# power_board2_v2_0.net
KiCad netlist of a schematic drawn in EAGLE
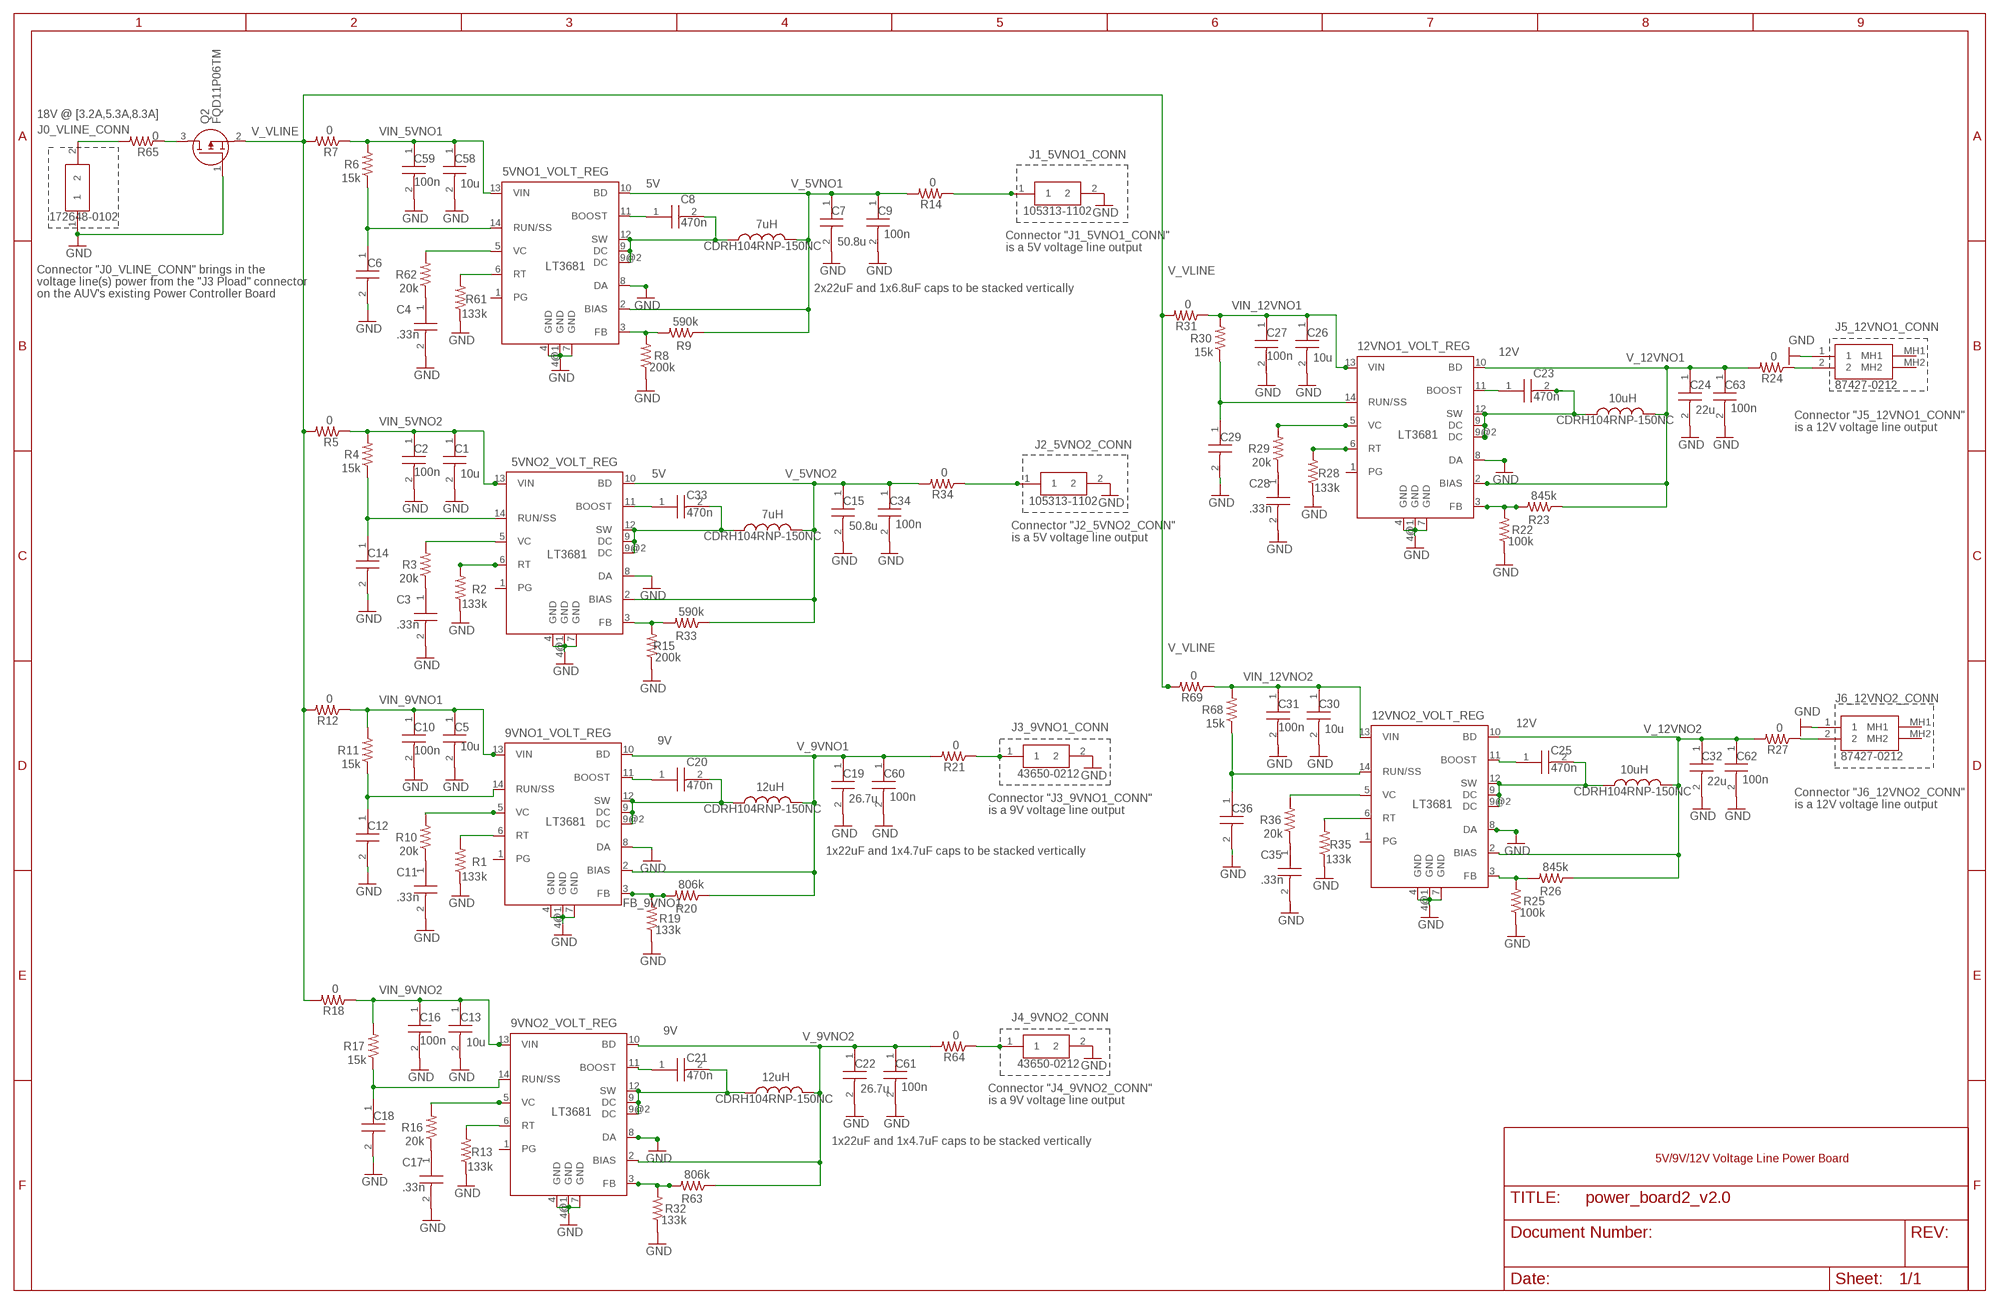
[diagram p0: schematic, sheet 1]

(export (version "E")
  (design (tool "Eeschema 10.0.6"))
  (components
    (comp (ref "5VNO1_VOLT_REG")
      (value "LT3681")
      (footprint "eagle-import:DFN14-4X3DE")
      (fields (field (name "MPN") "LT3681EDE#PBF"))
      (libsource (lib "eagle-import") (part "LT3681"))
    )
    (comp (ref "5VNO2_VOLT_REG")
      (value "LT3681")
      (footprint "eagle-import:DFN14-4X3DE")
      (fields (field (name "MPN") "LT3681EDE#PBF"))
      (libsource (lib "eagle-import") (part "LT3681"))
    )
    (comp (ref "9VNO1_VOLT_REG")
      (value "LT3681")
      (footprint "eagle-import:DFN14-4X3DE")
      (fields (field (name "MPN") "LT3681EDE#PBF"))
      (libsource (lib "eagle-import") (part "LT3681"))
    )
    (comp (ref "9VNO2_VOLT_REG")
      (value "LT3681")
      (footprint "eagle-import:DFN14-4X3DE")
      (fields (field (name "MPN") "LT3681EDE#PBF"))
      (libsource (lib "eagle-import") (part "LT3681"))
    )
    (comp (ref "12VNO1_VOLT_REG")
      (value "LT3681")
      (footprint "eagle-import:DFN14-4X3DE")
      (fields (field (name "MPN") "LT3681EDE#PBF"))
      (libsource (lib "eagle-import") (part "LT3681"))
    )
    (comp (ref "12VNO2_VOLT_REG")
      (value "LT3681")
      (footprint "eagle-import:DFN14-4X3DE")
      (fields (field (name "MPN") "LT3681EDE#PBF"))
      (libsource (lib "eagle-import") (part "LT3681"))
    )
    (comp (ref "C1")
      (value "10u")
      (footprint "eagle-import:CAPC5750X279N")
      (fields
        (field (name "MANUFACTURER_PART_NUMBER") "22201C106KAT2A")
        (field (name "MOUSER_PART_NUMBER") "581-22201C106KAT2A")
      )
      (libsource (lib "eagle-import") (part "22201C106KAT2A"))
    )
    (comp (ref "C2")
      (value "100n")
      (footprint "eagle-import:CAPC1608X90N")
      (fields
        (field (name "MANUFACTURER_PART_NUMBER") "06031C104KAT2A")
        (field (name "MOUSER_PART_NUMBER") "581-06031C104KAT2A")
      )
      (libsource (lib "eagle-import") (part "06031C104KAT2A"))
    )
    (comp (ref "C3")
      (value ".33n")
      (footprint "eagle-import:CAPC2012X140N")
      (fields
        (field (name "MANUFACTURER_PART_NUMBER") "08053C334KAT2A")
        (field (name "MOUSER_PART_NUMBER") "581-08053C334KAT2A")
        (field (name "RS_PART_NUMBER") "1747387")
      )
      (libsource (lib "eagle-import") (part "08053C334KAT2A"))
    )
    (comp (ref "C4")
      (value ".33n")
      (footprint "eagle-import:CAPC2012X140N")
      (fields
        (field (name "MANUFACTURER_PART_NUMBER") "08053C334KAT2A")
        (field (name "MOUSER_PART_NUMBER") "581-08053C334KAT2A")
        (field (name "RS_PART_NUMBER") "1747387")
      )
      (libsource (lib "eagle-import") (part "08053C334KAT2A"))
    )
    (comp (ref "C5")
      (value "10u")
      (footprint "eagle-import:CAPC5750X279N")
      (fields
        (field (name "MANUFACTURER_PART_NUMBER") "22201C106KAT2A")
        (field (name "MOUSER_PART_NUMBER") "581-22201C106KAT2A")
      )
      (libsource (lib "eagle-import") (part "22201C106KAT2A"))
    )
    (comp (ref "C6")
      (value "220n")
      (footprint "eagle-import:CAPC2012X140N")
      (fields
        (field (name "MANUFACTURER_PART_NUMBER") "08051C224KAT2A")
        (field (name "MOUSER_PART_NUMBER") "581-08051C224KAT2A")
      )
      (libsource (lib "eagle-import") (part "08051C224KAT2A"))
    )
    (comp (ref "C7")
      (value "50.8u")
      (footprint "eagle-import:CAPC3225X279N")
      (fields
        (field (name "MANUFACTURER_PART_NUMBER") "12103C226KAT2A")
        (field (name "MOUSER_PART_NUMBER") "581-12103C226KAT2A")
      )
      (libsource (lib "eagle-import") (part "12103C226KAT2A"))
    )
    (comp (ref "C8")
      (value "470n")
      (footprint "eagle-import:CAPC1608X90N")
      (fields
        (field (name "MANUFACTURER_PART_NUMBER") "06033C474JAT2A")
        (field (name "MOUSER_PART_NUMBER") "581-06033C474JAT2A")
      )
      (libsource (lib "eagle-import") (part "06033C474JAT2A"))
    )
    (comp (ref "C9")
      (value "100n")
      (footprint "eagle-import:CAPC1608X90N")
      (fields
        (field (name "MANUFACTURER_PART_NUMBER") "06033C104KAT4A")
        (field (name "MOUSER_PART_NUMBER") "581-06033C104KAT4A")
      )
      (libsource (lib "eagle-import") (part "06033C104KAT4A"))
    )
    (comp (ref "C10")
      (value "100n")
      (footprint "eagle-import:CAPC1608X90N")
      (fields
        (field (name "MANUFACTURER_PART_NUMBER") "06031C104KAT2A")
        (field (name "MOUSER_PART_NUMBER") "581-06031C104KAT2A")
      )
      (libsource (lib "eagle-import") (part "06031C104KAT2A"))
    )
    (comp (ref "C11")
      (value ".33n")
      (footprint "eagle-import:CAPC2012X140N")
      (fields
        (field (name "MANUFACTURER_PART_NUMBER") "08053C334KAT2A")
        (field (name "MOUSER_PART_NUMBER") "581-08053C334KAT2A")
        (field (name "RS_PART_NUMBER") "1747387")
      )
      (libsource (lib "eagle-import") (part "08053C334KAT2A"))
    )
    (comp (ref "C12")
      (value "220n")
      (footprint "eagle-import:CAPC2012X140N")
      (fields
        (field (name "MANUFACTURER_PART_NUMBER") "08051C224KAT2A")
        (field (name "MOUSER_PART_NUMBER") "581-08051C224KAT2A")
      )
      (libsource (lib "eagle-import") (part "08051C224KAT2A"))
    )
    (comp (ref "C13")
      (value "10u")
      (footprint "eagle-import:CAPC5750X279N")
      (fields
        (field (name "MANUFACTURER_PART_NUMBER") "22201C106KAT2A")
        (field (name "MOUSER_PART_NUMBER") "581-22201C106KAT2A")
      )
      (libsource (lib "eagle-import") (part "22201C106KAT2A"))
    )
    (comp (ref "C14")
      (value "220n")
      (footprint "eagle-import:CAPC2012X140N")
      (fields
        (field (name "MANUFACTURER_PART_NUMBER") "08051C224KAT2A")
        (field (name "MOUSER_PART_NUMBER") "581-08051C224KAT2A")
      )
      (libsource (lib "eagle-import") (part "08051C224KAT2A"))
    )
    (comp (ref "C15")
      (value "50.8u")
      (footprint "eagle-import:CAPC3225X279N")
      (fields
        (field (name "MANUFACTURER_PART_NUMBER") "12103C226KAT2A")
        (field (name "MOUSER_PART_NUMBER") "581-12103C226KAT2A")
      )
      (libsource (lib "eagle-import") (part "12103C226KAT2A"))
    )
    (comp (ref "C16")
      (value "100n")
      (footprint "eagle-import:CAPC1608X90N")
      (fields
        (field (name "MANUFACTURER_PART_NUMBER") "06031C104KAT2A")
        (field (name "MOUSER_PART_NUMBER") "581-06031C104KAT2A")
      )
      (libsource (lib "eagle-import") (part "06031C104KAT2A"))
    )
    (comp (ref "C17")
      (value ".33n")
      (footprint "eagle-import:CAPC2012X140N")
      (fields
        (field (name "MANUFACTURER_PART_NUMBER") "08053C334KAT2A")
        (field (name "MOUSER_PART_NUMBER") "581-08053C334KAT2A")
        (field (name "RS_PART_NUMBER") "1747387")
      )
      (libsource (lib "eagle-import") (part "08053C334KAT2A"))
    )
    (comp (ref "C18")
      (value "220n")
      (footprint "eagle-import:CAPC2012X140N")
      (fields
        (field (name "MANUFACTURER_PART_NUMBER") "08051C224KAT2A")
        (field (name "MOUSER_PART_NUMBER") "581-08051C224KAT2A")
      )
      (libsource (lib "eagle-import") (part "08051C224KAT2A"))
    )
    (comp (ref "C19")
      (value "26.7u")
      (footprint "eagle-import:CAPC3225X279N")
      (fields
        (field (name "MANUFACTURER_PART_NUMBER") "12103C226KAT2A")
        (field (name "MOUSER_PART_NUMBER") "581-12103C226KAT2A")
      )
      (libsource (lib "eagle-import") (part "12103C226KAT2A"))
    )
    (comp (ref "C20")
      (value "470n")
      (footprint "eagle-import:CAPC1608X90N")
      (fields
        (field (name "MANUFACTURER_PART_NUMBER") "06033C474JAT2A")
        (field (name "MOUSER_PART_NUMBER") "581-06033C474JAT2A")
      )
      (libsource (lib "eagle-import") (part "06033C474JAT2A"))
    )
    (comp (ref "C21")
      (value "470n")
      (footprint "eagle-import:CAPC1608X90N")
      (fields
        (field (name "MANUFACTURER_PART_NUMBER") "06033C474JAT2A")
        (field (name "MOUSER_PART_NUMBER") "581-06033C474JAT2A")
      )
      (libsource (lib "eagle-import") (part "06033C474JAT2A"))
    )
    (comp (ref "C22")
      (value "26.7u")
      (footprint "eagle-import:CAPC3225X279N")
      (fields
        (field (name "MANUFACTURER_PART_NUMBER") "12103C226KAT2A")
        (field (name "MOUSER_PART_NUMBER") "581-12103C226KAT2A")
      )
      (libsource (lib "eagle-import") (part "12103C226KAT2A"))
    )
    (comp (ref "C23")
      (value "470n")
      (footprint "eagle-import:CAPC1608X90N")
      (fields
        (field (name "MANUFACTURER_PART_NUMBER") "06033C474JAT2A")
        (field (name "MOUSER_PART_NUMBER") "581-06033C474JAT2A")
      )
      (libsource (lib "eagle-import") (part "06033C474JAT2A"))
    )
    (comp (ref "C24")
      (value "22u")
      (footprint "eagle-import:CAPC3225X279N")
      (fields
        (field (name "MANUFACTURER_PART_NUMBER") "12103C226KAT2A")
        (field (name "MOUSER_PART_NUMBER") "581-12103C226KAT2A")
      )
      (libsource (lib "eagle-import") (part "12103C226KAT2A"))
    )
    (comp (ref "C25")
      (value "470n")
      (footprint "eagle-import:CAPC1608X90N")
      (fields
        (field (name "MANUFACTURER_PART_NUMBER") "06033C474JAT2A")
        (field (name "MOUSER_PART_NUMBER") "581-06033C474JAT2A")
      )
      (libsource (lib "eagle-import") (part "06033C474JAT2A"))
    )
    (comp (ref "C26")
      (value "10u")
      (footprint "eagle-import:CAPC5750X279N")
      (fields
        (field (name "MANUFACTURER_PART_NUMBER") "22201C106KAT2A")
        (field (name "MOUSER_PART_NUMBER") "581-22201C106KAT2A")
      )
      (libsource (lib "eagle-import") (part "22201C106KAT2A"))
    )
    (comp (ref "C27")
      (value "100n")
      (footprint "eagle-import:CAPC1608X90N")
      (fields
        (field (name "MANUFACTURER_PART_NUMBER") "06031C104KAT2A")
        (field (name "MOUSER_PART_NUMBER") "581-06031C104KAT2A")
      )
      (libsource (lib "eagle-import") (part "06031C104KAT2A"))
    )
    (comp (ref "C28")
      (value ".33n")
      (footprint "eagle-import:CAPC2012X140N")
      (fields
        (field (name "MANUFACTURER_PART_NUMBER") "08053C334KAT2A")
        (field (name "MOUSER_PART_NUMBER") "581-08053C334KAT2A")
        (field (name "RS_PART_NUMBER") "1747387")
      )
      (libsource (lib "eagle-import") (part "08053C334KAT2A"))
    )
    (comp (ref "C29")
      (value "220n")
      (footprint "eagle-import:CAPC2012X140N")
      (fields
        (field (name "MANUFACTURER_PART_NUMBER") "08051C224KAT2A")
        (field (name "MOUSER_PART_NUMBER") "581-08051C224KAT2A")
      )
      (libsource (lib "eagle-import") (part "08051C224KAT2A"))
    )
    (comp (ref "C30")
      (value "10u")
      (footprint "eagle-import:CAPC5750X279N")
      (fields
        (field (name "MANUFACTURER_PART_NUMBER") "22201C106KAT2A")
        (field (name "MOUSER_PART_NUMBER") "581-22201C106KAT2A")
      )
      (libsource (lib "eagle-import") (part "22201C106KAT2A"))
    )
    (comp (ref "C31")
      (value "100n")
      (footprint "eagle-import:CAPC1608X90N")
      (fields
        (field (name "MANUFACTURER_PART_NUMBER") "06031C104KAT2A")
        (field (name "MOUSER_PART_NUMBER") "581-06031C104KAT2A")
      )
      (libsource (lib "eagle-import") (part "06031C104KAT2A"))
    )
    (comp (ref "C32")
      (value "22u")
      (footprint "eagle-import:CAPC3225X279N")
      (fields
        (field (name "MANUFACTURER_PART_NUMBER") "12103C226KAT2A")
        (field (name "MOUSER_PART_NUMBER") "581-12103C226KAT2A")
      )
      (libsource (lib "eagle-import") (part "12103C226KAT2A"))
    )
    (comp (ref "C33")
      (value "470n")
      (footprint "eagle-import:CAPC1608X90N")
      (fields
        (field (name "MANUFACTURER_PART_NUMBER") "06033C474JAT2A")
        (field (name "MOUSER_PART_NUMBER") "581-06033C474JAT2A")
      )
      (libsource (lib "eagle-import") (part "06033C474JAT2A"))
    )
    (comp (ref "C34")
      (value "100n")
      (footprint "eagle-import:CAPC1608X90N")
      (fields
        (field (name "MANUFACTURER_PART_NUMBER") "06033C104KAT4A")
        (field (name "MOUSER_PART_NUMBER") "581-06033C104KAT4A")
      )
      (libsource (lib "eagle-import") (part "06033C104KAT4A"))
    )
    (comp (ref "C35")
      (value ".33n")
      (footprint "eagle-import:CAPC2012X140N")
      (fields
        (field (name "MANUFACTURER_PART_NUMBER") "08053C334KAT2A")
        (field (name "MOUSER_PART_NUMBER") "581-08053C334KAT2A")
        (field (name "RS_PART_NUMBER") "1747387")
      )
      (libsource (lib "eagle-import") (part "08053C334KAT2A"))
    )
    (comp (ref "C36")
      (value "220n")
      (footprint "eagle-import:CAPC2012X140N")
      (fields
        (field (name "MANUFACTURER_PART_NUMBER") "08051C224KAT2A")
        (field (name "MOUSER_PART_NUMBER") "581-08051C224KAT2A")
      )
      (libsource (lib "eagle-import") (part "08051C224KAT2A"))
    )
    (comp (ref "C58")
      (value "10u")
      (footprint "eagle-import:CAPC5750X279N")
      (fields
        (field (name "MANUFACTURER_PART_NUMBER") "22201C106KAT2A")
        (field (name "MOUSER_PART_NUMBER") "581-22201C106KAT2A")
      )
      (libsource (lib "eagle-import") (part "22201C106KAT2A"))
    )
    (comp (ref "C59")
      (value "100n")
      (footprint "eagle-import:CAPC1608X90N")
      (fields
        (field (name "MANUFACTURER_PART_NUMBER") "06031C104KAT2A")
        (field (name "MOUSER_PART_NUMBER") "581-06031C104KAT2A")
      )
      (libsource (lib "eagle-import") (part "06031C104KAT2A"))
    )
    (comp (ref "C60")
      (value "100n")
      (footprint "eagle-import:CAPC1608X90N")
      (fields
        (field (name "MANUFACTURER_PART_NUMBER") "06033C104KAT4A")
        (field (name "MOUSER_PART_NUMBER") "581-06033C104KAT4A")
      )
      (libsource (lib "eagle-import") (part "06033C104KAT4A"))
    )
    (comp (ref "C61")
      (value "100n")
      (footprint "eagle-import:CAPC1608X90N")
      (fields
        (field (name "MANUFACTURER_PART_NUMBER") "06033C104KAT4A")
        (field (name "MOUSER_PART_NUMBER") "581-06033C104KAT4A")
      )
      (libsource (lib "eagle-import") (part "06033C104KAT4A"))
    )
    (comp (ref "C62")
      (value "100n")
      (footprint "eagle-import:CAPC1608X90N")
      (fields
        (field (name "MANUFACTURER_PART_NUMBER") "06033C104KAT4A")
        (field (name "MOUSER_PART_NUMBER") "581-06033C104KAT4A")
      )
      (libsource (lib "eagle-import") (part "06033C104KAT4A"))
    )
    (comp (ref "C63")
      (value "100n")
      (footprint "eagle-import:CAPC1608X90N")
      (fields
        (field (name "MANUFACTURER_PART_NUMBER") "06033C104KAT4A")
        (field (name "MOUSER_PART_NUMBER") "581-06033C104KAT4A")
      )
      (libsource (lib "eagle-import") (part "06033C104KAT4A"))
    )
    (comp (ref "INDUCTOR_2")
      (value "CDRH104RNP-150NC")
      (footprint "eagle-import:INDPM102100X400N")
      (fields (field (name "MOUSER_PART_NUMBER") "851-CDRH104RNP-150NC"))
      (libsource (lib "eagle-import") (part "CDRH104RNP-150NC"))
    )
    (comp (ref "INDUCTOR_4")
      (value "CDRH104RNP-150NC")
      (footprint "eagle-import:INDPM102100X400N")
      (fields (field (name "MOUSER_PART_NUMBER") "851-CDRH104RNP-150NC"))
      (libsource (lib "eagle-import") (part "CDRH104RNP-150NC"))
    )
    (comp (ref "INDUCTOR_5")
      (value "CDRH104RNP-150NC")
      (footprint "eagle-import:INDPM102100X400N")
      (fields (field (name "MOUSER_PART_NUMBER") "851-CDRH104RNP-150NC"))
      (libsource (lib "eagle-import") (part "CDRH104RNP-150NC"))
    )
    (comp (ref "INDUCTOR_6")
      (value "CDRH104RNP-150NC")
      (footprint "eagle-import:INDPM102100X400N")
      (fields (field (name "MOUSER_PART_NUMBER") "851-CDRH104RNP-150NC"))
      (libsource (lib "eagle-import") (part "CDRH104RNP-150NC"))
    )
    (comp (ref "INDUCTOR_7")
      (value "CDRH104RNP-150NC")
      (footprint "eagle-import:INDPM102100X400N")
      (fields (field (name "MOUSER_PART_NUMBER") "851-CDRH104RNP-150NC"))
      (libsource (lib "eagle-import") (part "CDRH104RNP-150NC"))
    )
    (comp (ref "INDUCTOR_8")
      (value "CDRH104RNP-150NC")
      (footprint "eagle-import:INDPM102100X400N")
      (fields (field (name "MOUSER_PART_NUMBER") "851-CDRH104RNP-150NC"))
      (libsource (lib "eagle-import") (part "CDRH104RNP-150NC"))
    )
    (comp (ref "J0_VLINE_CONN")
      (value "172648-0102")
      (footprint "eagle-import:1726480102")
      (fields (field (name "MOUSER_PART_NUMBER") "538-172648-0102"))
      (libsource (lib "eagle-import") (part "172648-0102"))
    )
    (comp (ref "J1_5VNO1_CONN")
      (value "105313-1102")
      (footprint "eagle-import:1053131102")
      (fields (field (name "MOUSER_PART_NUMBER") "538-105313-1102") (field (name "RS_PART_NUMBER") "1623686"))
      (libsource (lib "eagle-import") (part "105313-1102"))
    )
    (comp (ref "J2_5VNO2_CONN")
      (value "105313-1102")
      (footprint "eagle-import:1053131102")
      (fields (field (name "MOUSER_PART_NUMBER") "538-105313-1102") (field (name "RS_PART_NUMBER") "1623686"))
      (libsource (lib "eagle-import") (part "105313-1102"))
    )
    (comp (ref "J3_9VNO1_CONN")
      (value "43650-0212")
      (footprint "eagle-import:43650-0214")
      (fields (field (name "MOUSER_PART_NUMBER") "538-43650-0212") (field (name "RS_PART_NUMBER") "4476811P"))
      (libsource (lib "eagle-import") (part "43650-0212"))
    )
    (comp (ref "J4_9VNO2_CONN")
      (value "43650-0212")
      (footprint "eagle-import:43650-0214")
      (fields (field (name "MOUSER_PART_NUMBER") "538-43650-0212") (field (name "RS_PART_NUMBER") "4476811P"))
      (libsource (lib "eagle-import") (part "43650-0212"))
    )
    (comp (ref "J5_12VNO1_CONN")
      (value "87427-0212")
      (footprint "eagle-import:874270212")
      (fields (field (name "MOUSER_PART_NUMBER") "538-87427-0212"))
      (libsource (lib "eagle-import") (part "87427-0212"))
    )
    (comp (ref "J6_12VNO2_CONN")
      (value "87427-0212")
      (footprint "eagle-import:874270212")
      (fields (field (name "MOUSER_PART_NUMBER") "538-87427-0212"))
      (libsource (lib "eagle-import") (part "87427-0212"))
    )
    (comp (ref "Q2")
      (value "FQD11P06TM")
      (footprint "eagle-import:DPAK3-CASE-369AS")
      (fields (field (name "MOUSER_PART_NUMBER") "512-FQD11P06TM") (field (name "RS_PART_NUMBER") "6710949P"))
      (libsource (lib "eagle-import") (part "FQD11P06TM"))
    )
    (comp (ref "R1")
      (value "133k")
      (footprint "eagle-import:R0603")
      (libsource (lib "eagle-import") (part "R-US_R0603"))
    )
    (comp (ref "R2")
      (value "133k")
      (footprint "eagle-import:R0603")
      (libsource (lib "eagle-import") (part "R-US_R0603"))
    )
    (comp (ref "R3")
      (value "20k")
      (footprint "eagle-import:R0603")
      (libsource (lib "eagle-import") (part "R-US_R0603"))
    )
    (comp (ref "R4")
      (value "15k")
      (footprint "eagle-import:R0603")
      (libsource (lib "eagle-import") (part "R-US_R0603"))
    )
    (comp (ref "R5")
      (value "0")
      (footprint "eagle-import:0207_2V")
      (fields (field (name "MFR") "Yageo") (field (name "MPN") "RC0805FR-0710KL"))
      (libsource (lib "eagle-import") (part "R-US_0207/2V"))
    )
    (comp (ref "R6")
      (value "15k")
      (footprint "eagle-import:R0603")
      (libsource (lib "eagle-import") (part "R-US_R0603"))
    )
    (comp (ref "R7")
      (value "0")
      (footprint "eagle-import:0207_2V")
      (fields (field (name "MFR") "Yageo") (field (name "MPN") "RC0805FR-0710KL"))
      (libsource (lib "eagle-import") (part "R-US_0207/2V"))
    )
    (comp (ref "R8")
      (value "200k")
      (footprint "eagle-import:R0603")
      (libsource (lib "eagle-import") (part "R-US_R0603"))
    )
    (comp (ref "R9")
      (value "590k")
      (footprint "eagle-import:R0603")
      (libsource (lib "eagle-import") (part "R-US_R0603"))
    )
    (comp (ref "R10")
      (value "20k")
      (footprint "eagle-import:R0603")
      (libsource (lib "eagle-import") (part "R-US_R0603"))
    )
    (comp (ref "R11")
      (value "15k")
      (footprint "eagle-import:R0603")
      (libsource (lib "eagle-import") (part "R-US_R0603"))
    )
    (comp (ref "R12")
      (value "0")
      (footprint "eagle-import:0207_2V")
      (fields (field (name "MFR") "Yageo") (field (name "MPN") "RC0805FR-0710KL"))
      (libsource (lib "eagle-import") (part "R-US_0207/2V"))
    )
    (comp (ref "R13")
      (value "133k")
      (footprint "eagle-import:R0603")
      (libsource (lib "eagle-import") (part "R-US_R0603"))
    )
    (comp (ref "R14")
      (value "0")
      (footprint "eagle-import:0207_2V")
      (fields (field (name "MFR") "Yageo") (field (name "MPN") "RC0805FR-0710KL"))
      (libsource (lib "eagle-import") (part "R-US_0207/2V"))
    )
    (comp (ref "R15")
      (value "200k")
      (footprint "eagle-import:R0603")
      (libsource (lib "eagle-import") (part "R-US_R0603"))
    )
    (comp (ref "R16")
      (value "20k")
      (footprint "eagle-import:R0603")
      (libsource (lib "eagle-import") (part "R-US_R0603"))
    )
    (comp (ref "R17")
      (value "15k")
      (footprint "eagle-import:R0603")
      (libsource (lib "eagle-import") (part "R-US_R0603"))
    )
    (comp (ref "R18")
      (value "0")
      (footprint "eagle-import:0207_2V")
      (fields (field (name "MFR") "Yageo") (field (name "MPN") "RC0805FR-0710KL"))
      (libsource (lib "eagle-import") (part "R-US_0207/2V"))
    )
    (comp (ref "R19")
      (value "133k")
      (footprint "eagle-import:R0603")
      (libsource (lib "eagle-import") (part "R-US_R0603"))
    )
    (comp (ref "R20")
      (value "806k")
      (footprint "eagle-import:R0603")
      (libsource (lib "eagle-import") (part "R-US_R0603"))
    )
    (comp (ref "R21")
      (value "0")
      (footprint "eagle-import:0207_2V")
      (fields (field (name "MFR") "Yageo") (field (name "MPN") "RC0805FR-0710KL"))
      (libsource (lib "eagle-import") (part "R-US_0207/2V"))
    )
    (comp (ref "R22")
      (value "100k")
      (footprint "eagle-import:R0603")
      (libsource (lib "eagle-import") (part "R-US_R0603"))
    )
    (comp (ref "R23")
      (value "845k")
      (footprint "eagle-import:R0603")
      (libsource (lib "eagle-import") (part "R-US_R0603"))
    )
    (comp (ref "R24")
      (value "0")
      (footprint "eagle-import:0207_2V")
      (fields (field (name "MFR") "Yageo") (field (name "MPN") "RC0805FR-0710KL"))
      (libsource (lib "eagle-import") (part "R-US_0207/2V"))
    )
    (comp (ref "R25")
      (value "100k")
      (footprint "eagle-import:R0603")
      (libsource (lib "eagle-import") (part "R-US_R0603"))
    )
    (comp (ref "R26")
      (value "845k")
      (footprint "eagle-import:R0603")
      (libsource (lib "eagle-import") (part "R-US_R0603"))
    )
    (comp (ref "R27")
      (value "0")
      (footprint "eagle-import:0207_2V")
      (fields (field (name "MFR") "Yageo") (field (name "MPN") "RC0805FR-0710KL"))
      (libsource (lib "eagle-import") (part "R-US_0207/2V"))
    )
    (comp (ref "R28")
      (value "133k")
      (footprint "eagle-import:R0603")
      (libsource (lib "eagle-import") (part "R-US_R0603"))
    )
    (comp (ref "R29")
      (value "20k")
      (footprint "eagle-import:R0603")
      (libsource (lib "eagle-import") (part "R-US_R0603"))
    )
    (comp (ref "R30")
      (value "15k")
      (footprint "eagle-import:R0603")
      (libsource (lib "eagle-import") (part "R-US_R0603"))
    )
    (comp (ref "R31")
      (value "0")
      (footprint "eagle-import:0207_2V")
      (fields (field (name "MFR") "Yageo") (field (name "MPN") "RC0805FR-0710KL"))
      (libsource (lib "eagle-import") (part "R-US_0207/2V"))
    )
    (comp (ref "R32")
      (value "133k")
      (footprint "eagle-import:R0603")
      (libsource (lib "eagle-import") (part "R-US_R0603"))
    )
    (comp (ref "R33")
      (value "590k")
      (footprint "eagle-import:R0603")
      (libsource (lib "eagle-import") (part "R-US_R0603"))
    )
    (comp (ref "R34")
      (value "0")
      (footprint "eagle-import:0207_2V")
      (fields (field (name "MFR") "Yageo") (field (name "MPN") "RC0805FR-0710KL"))
      (libsource (lib "eagle-import") (part "R-US_0207/2V"))
    )
    (comp (ref "R35")
      (value "133k")
      (footprint "eagle-import:R0603")
      (libsource (lib "eagle-import") (part "R-US_R0603"))
    )
    (comp (ref "R36")
      (value "20k")
      (footprint "eagle-import:R0603")
      (libsource (lib "eagle-import") (part "R-US_R0603"))
    )
    (comp (ref "R61")
      (value "133k")
      (footprint "eagle-import:R0603")
      (libsource (lib "eagle-import") (part "R-US_R0603"))
    )
    (comp (ref "R62")
      (value "20k")
      (footprint "eagle-import:R0603")
      (libsource (lib "eagle-import") (part "R-US_R0603"))
    )
    (comp (ref "R63")
      (value "806k")
      (footprint "eagle-import:R0603")
      (libsource (lib "eagle-import") (part "R-US_R0603"))
    )
    (comp (ref "R64")
      (value "0")
      (footprint "eagle-import:0207_2V")
      (fields (field (name "MFR") "Yageo") (field (name "MPN") "RC0805FR-0710KL"))
      (libsource (lib "eagle-import") (part "R-US_0207/2V"))
    )
    (comp (ref "R65")
      (value "0")
      (footprint "eagle-import:0207_2V")
      (fields (field (name "MFR") "Yageo") (field (name "MPN") "RC0805FR-0710KL"))
      (libsource (lib "eagle-import") (part "R-US_0207/2V"))
    )
    (comp (ref "R68")
      (value "15k")
      (footprint "eagle-import:R0603")
      (libsource (lib "eagle-import") (part "R-US_R0603"))
    )
    (comp (ref "R69")
      (value "0")
      (footprint "eagle-import:0207_2V")
      (fields (field (name "MFR") "Yageo") (field (name "MPN") "RC0805FR-0710KL"))
      (libsource (lib "eagle-import") (part "R-US_0207/2V"))
    )
  )
  (nets
    (net (code "1") (name "/FB_9VNO1") (class "Default")
      (node (ref "9VNO1_VOLT_REG") (pin "3") (pinfunction "FB_3") (pintype "input"))
      (node (ref "R19") (pin "2") (pinfunction "2_2") (pintype "passive"))
      (node (ref "R20") (pin "2") (pinfunction "2_2") (pintype "passive"))
    )
    (net (code "2") (name "/VIN_5VNO1") (class "Default")
      (node (ref "5VNO1_VOLT_REG") (pin "13") (pinfunction "VIN_13") (pintype "input"))
      (node (ref "C58") (pin "1") (pinfunction "1_1") (pintype "bidirectional"))
      (node (ref "C59") (pin "1") (pinfunction "1_1") (pintype "bidirectional"))
      (node (ref "R6") (pin "2") (pinfunction "2_2") (pintype "passive"))
      (node (ref "R7") (pin "1") (pinfunction "1_1") (pintype "passive"))
    )
    (net (code "3") (name "/VIN_5VNO2") (class "Default")
      (node (ref "5VNO2_VOLT_REG") (pin "13") (pinfunction "VIN_13") (pintype "input"))
      (node (ref "C1") (pin "1") (pinfunction "1_1") (pintype "bidirectional"))
      (node (ref "C2") (pin "1") (pinfunction "1_1") (pintype "bidirectional"))
      (node (ref "R4") (pin "2") (pinfunction "2_2") (pintype "passive"))
      (node (ref "R5") (pin "1") (pinfunction "1_1") (pintype "passive"))
    )
    (net (code "4") (name "/VIN_9VNO1") (class "Default")
      (node (ref "9VNO1_VOLT_REG") (pin "13") (pinfunction "VIN_13") (pintype "input"))
      (node (ref "C10") (pin "1") (pinfunction "1_1") (pintype "bidirectional"))
      (node (ref "C5") (pin "1") (pinfunction "1_1") (pintype "bidirectional"))
      (node (ref "R11") (pin "2") (pinfunction "2_2") (pintype "passive"))
      (node (ref "R12") (pin "1") (pinfunction "1_1") (pintype "passive"))
    )
    (net (code "5") (name "/VIN_9VNO2") (class "Default")
      (node (ref "9VNO2_VOLT_REG") (pin "13") (pinfunction "VIN_13") (pintype "input"))
      (node (ref "C13") (pin "1") (pinfunction "1_1") (pintype "bidirectional"))
      (node (ref "C16") (pin "1") (pinfunction "1_1") (pintype "bidirectional"))
      (node (ref "R17") (pin "2") (pinfunction "2_2") (pintype "passive"))
      (node (ref "R18") (pin "1") (pinfunction "1_1") (pintype "passive"))
    )
    (net (code "6") (name "/VIN_12VNO1") (class "Default")
      (node (ref "12VNO1_VOLT_REG") (pin "13") (pinfunction "VIN_13") (pintype "input"))
      (node (ref "C26") (pin "1") (pinfunction "1_1") (pintype "bidirectional"))
      (node (ref "C27") (pin "1") (pinfunction "1_1") (pintype "bidirectional"))
      (node (ref "R30") (pin "2") (pinfunction "2_2") (pintype "passive"))
      (node (ref "R31") (pin "1") (pinfunction "1_1") (pintype "passive"))
    )
    (net (code "7") (name "/VIN_12VNO2") (class "Default")
      (node (ref "12VNO2_VOLT_REG") (pin "13") (pinfunction "VIN_13") (pintype "input"))
      (node (ref "C30") (pin "1") (pinfunction "1_1") (pintype "bidirectional"))
      (node (ref "C31") (pin "1") (pinfunction "1_1") (pintype "bidirectional"))
      (node (ref "R68") (pin "2") (pinfunction "2_2") (pintype "passive"))
      (node (ref "R69") (pin "1") (pinfunction "1_1") (pintype "passive"))
    )
    (net (code "8") (name "/V_5VNO1") (class "Default")
      (node (ref "5VNO1_VOLT_REG") (pin "10") (pinfunction "BD_10") (pintype "input"))
      (node (ref "5VNO1_VOLT_REG") (pin "2") (pinfunction "BIAS_2") (pintype "input"))
      (node (ref "C7") (pin "1") (pinfunction "1_1") (pintype "bidirectional"))
      (node (ref "C9") (pin "1") (pinfunction "1_1") (pintype "bidirectional"))
      (node (ref "INDUCTOR_2") (pin "2") (pinfunction "2_2") (pintype "passive"))
      (node (ref "R14") (pin "2") (pinfunction "2_2") (pintype "passive"))
      (node (ref "R9") (pin "1") (pinfunction "1_1") (pintype "passive"))
    )
    (net (code "9") (name "/V_5VNO2") (class "Default")
      (node (ref "5VNO2_VOLT_REG") (pin "10") (pinfunction "BD_10") (pintype "input"))
      (node (ref "5VNO2_VOLT_REG") (pin "2") (pinfunction "BIAS_2") (pintype "input"))
      (node (ref "C15") (pin "1") (pinfunction "1_1") (pintype "bidirectional"))
      (node (ref "C34") (pin "1") (pinfunction "1_1") (pintype "bidirectional"))
      (node (ref "INDUCTOR_4") (pin "2") (pinfunction "2_2") (pintype "passive"))
      (node (ref "R33") (pin "1") (pinfunction "1_1") (pintype "passive"))
      (node (ref "R34") (pin "2") (pinfunction "2_2") (pintype "passive"))
    )
    (net (code "10") (name "/V_9VNO1") (class "Default")
      (node (ref "9VNO1_VOLT_REG") (pin "10") (pinfunction "BD_10") (pintype "input"))
      (node (ref "9VNO1_VOLT_REG") (pin "2") (pinfunction "BIAS_2") (pintype "input"))
      (node (ref "C19") (pin "1") (pinfunction "1_1") (pintype "bidirectional"))
      (node (ref "C60") (pin "1") (pinfunction "1_1") (pintype "bidirectional"))
      (node (ref "INDUCTOR_5") (pin "2") (pinfunction "2_2") (pintype "passive"))
      (node (ref "R20") (pin "1") (pinfunction "1_1") (pintype "passive"))
      (node (ref "R21") (pin "2") (pinfunction "2_2") (pintype "passive"))
    )
    (net (code "11") (name "/V_9VNO2") (class "Default")
      (node (ref "9VNO2_VOLT_REG") (pin "10") (pinfunction "BD_10") (pintype "input"))
      (node (ref "9VNO2_VOLT_REG") (pin "2") (pinfunction "BIAS_2") (pintype "input"))
      (node (ref "C22") (pin "1") (pinfunction "1_1") (pintype "bidirectional"))
      (node (ref "C61") (pin "1") (pinfunction "1_1") (pintype "bidirectional"))
      (node (ref "INDUCTOR_6") (pin "2") (pinfunction "2_2") (pintype "passive"))
      (node (ref "R63") (pin "1") (pinfunction "1_1") (pintype "passive"))
      (node (ref "R64") (pin "2") (pinfunction "2_2") (pintype "passive"))
    )
    (net (code "12") (name "/V_12VNO1") (class "Default")
      (node (ref "12VNO1_VOLT_REG") (pin "10") (pinfunction "BD_10") (pintype "input"))
      (node (ref "12VNO1_VOLT_REG") (pin "2") (pinfunction "BIAS_2") (pintype "input"))
      (node (ref "C24") (pin "1") (pinfunction "1_1") (pintype "bidirectional"))
      (node (ref "C63") (pin "1") (pinfunction "1_1") (pintype "bidirectional"))
      (node (ref "INDUCTOR_7") (pin "2") (pinfunction "2_2") (pintype "passive"))
      (node (ref "R23") (pin "1") (pinfunction "1_1") (pintype "passive"))
      (node (ref "R24") (pin "2") (pinfunction "2_2") (pintype "passive"))
    )
    (net (code "13") (name "/V_12VNO2") (class "Default")
      (node (ref "12VNO2_VOLT_REG") (pin "10") (pinfunction "BD_10") (pintype "input"))
      (node (ref "12VNO2_VOLT_REG") (pin "2") (pinfunction "BIAS_2") (pintype "input"))
      (node (ref "C32") (pin "1") (pinfunction "1_1") (pintype "bidirectional"))
      (node (ref "C62") (pin "1") (pinfunction "1_1") (pintype "bidirectional"))
      (node (ref "INDUCTOR_8") (pin "2") (pinfunction "2_2") (pintype "passive"))
      (node (ref "R26") (pin "1") (pinfunction "1_1") (pintype "passive"))
      (node (ref "R27") (pin "2") (pinfunction "2_2") (pintype "passive"))
    )
    (net (code "14") (name "/V_VLINE") (class "Default")
      (node (ref "Q2") (pin "2") (pinfunction "S_2") (pintype "bidirectional"))
      (node (ref "R12") (pin "2") (pinfunction "2_2") (pintype "passive"))
      (node (ref "R18") (pin "2") (pinfunction "2_2") (pintype "passive"))
      (node (ref "R31") (pin "2") (pinfunction "2_2") (pintype "passive"))
      (node (ref "R5") (pin "2") (pinfunction "2_2") (pintype "passive"))
      (node (ref "R69") (pin "2") (pinfunction "2_2") (pintype "passive"))
      (node (ref "R7") (pin "2") (pinfunction "2_2") (pintype "passive"))
    )
    (net (code "15") (name "GND") (class "Default")
      (node (ref "12VNO1_VOLT_REG") (pin "4") (pinfunction "GND_4") (pintype "input"))
      (node (ref "12VNO1_VOLT_REG") (pin "4@1") (pinfunction "GND_4@1") (pintype "input"))
      (node (ref "12VNO1_VOLT_REG") (pin "7") (pinfunction "GND_7") (pintype "input"))
      (node (ref "12VNO1_VOLT_REG") (pin "8") (pinfunction "DA_8") (pintype "passive"))
      (node (ref "12VNO2_VOLT_REG") (pin "4") (pinfunction "GND_4") (pintype "input"))
      (node (ref "12VNO2_VOLT_REG") (pin "4@1") (pinfunction "GND_4@1") (pintype "input"))
      (node (ref "12VNO2_VOLT_REG") (pin "7") (pinfunction "GND_7") (pintype "input"))
      (node (ref "5VNO1_VOLT_REG") (pin "4") (pinfunction "GND_4") (pintype "input"))
      (node (ref "5VNO1_VOLT_REG") (pin "4@1") (pinfunction "GND_4@1") (pintype "input"))
      (node (ref "5VNO1_VOLT_REG") (pin "7") (pinfunction "GND_7") (pintype "input"))
      (node (ref "5VNO1_VOLT_REG") (pin "8") (pinfunction "DA_8") (pintype "passive"))
      (node (ref "5VNO2_VOLT_REG") (pin "4") (pinfunction "GND_4") (pintype "input"))
      (node (ref "5VNO2_VOLT_REG") (pin "4@1") (pinfunction "GND_4@1") (pintype "input"))
      (node (ref "5VNO2_VOLT_REG") (pin "7") (pinfunction "GND_7") (pintype "input"))
      (node (ref "5VNO2_VOLT_REG") (pin "8") (pinfunction "DA_8") (pintype "passive"))
      (node (ref "9VNO1_VOLT_REG") (pin "4") (pinfunction "GND_4") (pintype "input"))
      (node (ref "9VNO1_VOLT_REG") (pin "4@1") (pinfunction "GND_4@1") (pintype "input"))
      (node (ref "9VNO1_VOLT_REG") (pin "7") (pinfunction "GND_7") (pintype "input"))
      (node (ref "9VNO1_VOLT_REG") (pin "8") (pinfunction "DA_8") (pintype "passive"))
      (node (ref "9VNO2_VOLT_REG") (pin "4") (pinfunction "GND_4") (pintype "input"))
      (node (ref "9VNO2_VOLT_REG") (pin "4@1") (pinfunction "GND_4@1") (pintype "input"))
      (node (ref "9VNO2_VOLT_REG") (pin "7") (pinfunction "GND_7") (pintype "input"))
      (node (ref "9VNO2_VOLT_REG") (pin "8") (pinfunction "DA_8") (pintype "passive"))
      (node (ref "C1") (pin "2") (pinfunction "2_2") (pintype "bidirectional"))
      (node (ref "C10") (pin "2") (pinfunction "2_2") (pintype "bidirectional"))
      (node (ref "C11") (pin "2") (pinfunction "2_2") (pintype "bidirectional"))
      (node (ref "C12") (pin "2") (pinfunction "2_2") (pintype "bidirectional"))
      (node (ref "C13") (pin "2") (pinfunction "2_2") (pintype "bidirectional"))
      (node (ref "C14") (pin "2") (pinfunction "2_2") (pintype "bidirectional"))
      (node (ref "C15") (pin "2") (pinfunction "2_2") (pintype "bidirectional"))
      (node (ref "C16") (pin "2") (pinfunction "2_2") (pintype "bidirectional"))
      (node (ref "C17") (pin "2") (pinfunction "2_2") (pintype "bidirectional"))
      (node (ref "C18") (pin "2") (pinfunction "2_2") (pintype "bidirectional"))
      (node (ref "C19") (pin "2") (pinfunction "2_2") (pintype "bidirectional"))
      (node (ref "C2") (pin "2") (pinfunction "2_2") (pintype "bidirectional"))
      (node (ref "C22") (pin "2") (pinfunction "2_2") (pintype "bidirectional"))
      (node (ref "C24") (pin "2") (pinfunction "2_2") (pintype "bidirectional"))
      (node (ref "C26") (pin "2") (pinfunction "2_2") (pintype "bidirectional"))
      (node (ref "C27") (pin "2") (pinfunction "2_2") (pintype "bidirectional"))
      (node (ref "C28") (pin "2") (pinfunction "2_2") (pintype "bidirectional"))
      (node (ref "C29") (pin "2") (pinfunction "2_2") (pintype "bidirectional"))
      (node (ref "C3") (pin "2") (pinfunction "2_2") (pintype "bidirectional"))
      (node (ref "C30") (pin "2") (pinfunction "2_2") (pintype "bidirectional"))
      (node (ref "C31") (pin "2") (pinfunction "2_2") (pintype "bidirectional"))
      (node (ref "C32") (pin "2") (pinfunction "2_2") (pintype "bidirectional"))
      (node (ref "C34") (pin "2") (pinfunction "2_2") (pintype "bidirectional"))
      (node (ref "C35") (pin "2") (pinfunction "2_2") (pintype "bidirectional"))
      (node (ref "C36") (pin "2") (pinfunction "2_2") (pintype "bidirectional"))
      (node (ref "C4") (pin "2") (pinfunction "2_2") (pintype "bidirectional"))
      (node (ref "C5") (pin "2") (pinfunction "2_2") (pintype "bidirectional"))
      (node (ref "C58") (pin "2") (pinfunction "2_2") (pintype "bidirectional"))
      (node (ref "C59") (pin "2") (pinfunction "2_2") (pintype "bidirectional"))
      (node (ref "C6") (pin "2") (pinfunction "2_2") (pintype "bidirectional"))
      (node (ref "C60") (pin "2") (pinfunction "2_2") (pintype "bidirectional"))
      (node (ref "C61") (pin "2") (pinfunction "2_2") (pintype "bidirectional"))
      (node (ref "C62") (pin "2") (pinfunction "2_2") (pintype "bidirectional"))
      (node (ref "C63") (pin "2") (pinfunction "2_2") (pintype "bidirectional"))
      (node (ref "C7") (pin "2") (pinfunction "2_2") (pintype "bidirectional"))
      (node (ref "C9") (pin "2") (pinfunction "2_2") (pintype "bidirectional"))
      (node (ref "J0_VLINE_CONN") (pin "1") (pinfunction "1_1") (pintype "bidirectional"))
      (node (ref "J1_5VNO1_CONN") (pin "2") (pinfunction "2_2") (pintype "bidirectional"))
      (node (ref "J2_5VNO2_CONN") (pin "2") (pinfunction "2_2") (pintype "bidirectional"))
      (node (ref "J3_9VNO1_CONN") (pin "2") (pinfunction "2_2") (pintype "bidirectional"))
      (node (ref "J4_9VNO2_CONN") (pin "2") (pinfunction "2_2") (pintype "bidirectional"))
      (node (ref "J5_12VNO1_CONN") (pin "1") (pinfunction "1_1") (pintype "bidirectional"))
      (node (ref "J6_12VNO2_CONN") (pin "1") (pinfunction "1_1") (pintype "bidirectional"))
      (node (ref "Q2") (pin "1") (pinfunction "G_1") (pintype "bidirectional"))
      (node (ref "R1") (pin "1") (pinfunction "1_1") (pintype "passive"))
      (node (ref "R13") (pin "1") (pinfunction "1_1") (pintype "passive"))
      (node (ref "R15") (pin "1") (pinfunction "1_1") (pintype "passive"))
      (node (ref "R19") (pin "1") (pinfunction "1_1") (pintype "passive"))
      (node (ref "R2") (pin "1") (pinfunction "1_1") (pintype "passive"))
      (node (ref "R22") (pin "1") (pinfunction "1_1") (pintype "passive"))
      (node (ref "R25") (pin "1") (pinfunction "1_1") (pintype "passive"))
      (node (ref "R28") (pin "1") (pinfunction "1_1") (pintype "passive"))
      (node (ref "R32") (pin "1") (pinfunction "1_1") (pintype "passive"))
      (node (ref "R35") (pin "1") (pinfunction "1_1") (pintype "passive"))
      (node (ref "R61") (pin "1") (pinfunction "1_1") (pintype "passive"))
      (node (ref "R8") (pin "1") (pinfunction "1_1") (pintype "passive"))
    )
    (net (code "16") (name "Net-(5VNO1_VOLT_REG-BOOST)") (class "Default")
      (node (ref "5VNO1_VOLT_REG") (pin "11") (pinfunction "BOOST_11") (pintype "output"))
      (node (ref "C8") (pin "1") (pinfunction "1_1") (pintype "bidirectional"))
    )
    (net (code "17") (name "Net-(5VNO1_VOLT_REG-FB)") (class "Default")
      (node (ref "5VNO1_VOLT_REG") (pin "3") (pinfunction "FB_3") (pintype "input"))
      (node (ref "R8") (pin "2") (pinfunction "2_2") (pintype "passive"))
      (node (ref "R9") (pin "2") (pinfunction "2_2") (pintype "passive"))
    )
    (net (code "18") (name "Net-(5VNO1_VOLT_REG-RT)") (class "Default")
      (node (ref "5VNO1_VOLT_REG") (pin "6") (pinfunction "RT_6") (pintype "input"))
      (node (ref "R61") (pin "2") (pinfunction "2_2") (pintype "passive"))
    )
    (net (code "19") (name "Net-(5VNO1_VOLT_REG-RUN{slash}SS)") (class "Default")
      (node (ref "5VNO1_VOLT_REG") (pin "14") (pinfunction "RUN/SS_14") (pintype "input"))
      (node (ref "C6") (pin "1") (pinfunction "1_1") (pintype "bidirectional"))
      (node (ref "R6") (pin "1") (pinfunction "1_1") (pintype "passive"))
    )
    (net (code "20") (name "Net-(5VNO1_VOLT_REG-SW)") (class "Default")
      (node (ref "5VNO1_VOLT_REG") (pin "12") (pinfunction "SW_12") (pintype "output"))
      (node (ref "5VNO1_VOLT_REG") (pin "9") (pinfunction "DC_9") (pintype "passive"))
      (node (ref "5VNO1_VOLT_REG") (pin "9@2") (pinfunction "DC_9@2") (pintype "passive"))
      (node (ref "C8") (pin "2") (pinfunction "2_2") (pintype "bidirectional"))
      (node (ref "INDUCTOR_2") (pin "1") (pinfunction "1_1") (pintype "passive"))
    )
    (net (code "21") (name "Net-(5VNO1_VOLT_REG-VC)") (class "Default")
      (node (ref "5VNO1_VOLT_REG") (pin "5") (pinfunction "VC_5") (pintype "output"))
      (node (ref "R62") (pin "2") (pinfunction "2_2") (pintype "passive"))
    )
    (net (code "22") (name "Net-(5VNO2_VOLT_REG-BOOST)") (class "Default")
      (node (ref "5VNO2_VOLT_REG") (pin "11") (pinfunction "BOOST_11") (pintype "output"))
      (node (ref "C33") (pin "1") (pinfunction "1_1") (pintype "bidirectional"))
    )
    (net (code "23") (name "Net-(5VNO2_VOLT_REG-FB)") (class "Default")
      (node (ref "5VNO2_VOLT_REG") (pin "3") (pinfunction "FB_3") (pintype "input"))
      (node (ref "R15") (pin "2") (pinfunction "2_2") (pintype "passive"))
      (node (ref "R33") (pin "2") (pinfunction "2_2") (pintype "passive"))
    )
    (net (code "24") (name "Net-(5VNO2_VOLT_REG-RT)") (class "Default")
      (node (ref "5VNO2_VOLT_REG") (pin "6") (pinfunction "RT_6") (pintype "input"))
      (node (ref "R2") (pin "2") (pinfunction "2_2") (pintype "passive"))
    )
    (net (code "25") (name "Net-(5VNO2_VOLT_REG-RUN{slash}SS)") (class "Default")
      (node (ref "5VNO2_VOLT_REG") (pin "14") (pinfunction "RUN/SS_14") (pintype "input"))
      (node (ref "C14") (pin "1") (pinfunction "1_1") (pintype "bidirectional"))
      (node (ref "R4") (pin "1") (pinfunction "1_1") (pintype "passive"))
    )
    (net (code "26") (name "Net-(5VNO2_VOLT_REG-SW)") (class "Default")
      (node (ref "5VNO2_VOLT_REG") (pin "12") (pinfunction "SW_12") (pintype "output"))
      (node (ref "5VNO2_VOLT_REG") (pin "9") (pinfunction "DC_9") (pintype "passive"))
      (node (ref "5VNO2_VOLT_REG") (pin "9@2") (pinfunction "DC_9@2") (pintype "passive"))
      (node (ref "C33") (pin "2") (pinfunction "2_2") (pintype "bidirectional"))
      (node (ref "INDUCTOR_4") (pin "1") (pinfunction "1_1") (pintype "passive"))
    )
    (net (code "27") (name "Net-(5VNO2_VOLT_REG-VC)") (class "Default")
      (node (ref "5VNO2_VOLT_REG") (pin "5") (pinfunction "VC_5") (pintype "output"))
      (node (ref "R3") (pin "2") (pinfunction "2_2") (pintype "passive"))
    )
    (net (code "28") (name "Net-(9VNO1_VOLT_REG-BOOST)") (class "Default")
      (node (ref "9VNO1_VOLT_REG") (pin "11") (pinfunction "BOOST_11") (pintype "output"))
      (node (ref "C20") (pin "1") (pinfunction "1_1") (pintype "bidirectional"))
    )
    (net (code "29") (name "Net-(9VNO1_VOLT_REG-RT)") (class "Default")
      (node (ref "9VNO1_VOLT_REG") (pin "6") (pinfunction "RT_6") (pintype "input"))
      (node (ref "R1") (pin "2") (pinfunction "2_2") (pintype "passive"))
    )
    (net (code "30") (name "Net-(9VNO1_VOLT_REG-RUN{slash}SS)") (class "Default")
      (node (ref "9VNO1_VOLT_REG") (pin "14") (pinfunction "RUN/SS_14") (pintype "input"))
      (node (ref "C12") (pin "1") (pinfunction "1_1") (pintype "bidirectional"))
      (node (ref "R11") (pin "1") (pinfunction "1_1") (pintype "passive"))
    )
    (net (code "31") (name "Net-(9VNO1_VOLT_REG-SW)") (class "Default")
      (node (ref "9VNO1_VOLT_REG") (pin "12") (pinfunction "SW_12") (pintype "output"))
      (node (ref "9VNO1_VOLT_REG") (pin "9") (pinfunction "DC_9") (pintype "passive"))
      (node (ref "9VNO1_VOLT_REG") (pin "9@2") (pinfunction "DC_9@2") (pintype "passive"))
      (node (ref "C20") (pin "2") (pinfunction "2_2") (pintype "bidirectional"))
      (node (ref "INDUCTOR_5") (pin "1") (pinfunction "1_1") (pintype "passive"))
    )
    (net (code "32") (name "Net-(9VNO1_VOLT_REG-VC)") (class "Default")
      (node (ref "9VNO1_VOLT_REG") (pin "5") (pinfunction "VC_5") (pintype "output"))
      (node (ref "R10") (pin "2") (pinfunction "2_2") (pintype "passive"))
    )
    (net (code "33") (name "Net-(9VNO2_VOLT_REG-BOOST)") (class "Default")
      (node (ref "9VNO2_VOLT_REG") (pin "11") (pinfunction "BOOST_11") (pintype "output"))
      (node (ref "C21") (pin "1") (pinfunction "1_1") (pintype "bidirectional"))
    )
    (net (code "34") (name "Net-(9VNO2_VOLT_REG-FB)") (class "Default")
      (node (ref "9VNO2_VOLT_REG") (pin "3") (pinfunction "FB_3") (pintype "input"))
      (node (ref "R32") (pin "2") (pinfunction "2_2") (pintype "passive"))
      (node (ref "R63") (pin "2") (pinfunction "2_2") (pintype "passive"))
    )
    (net (code "35") (name "Net-(9VNO2_VOLT_REG-RT)") (class "Default")
      (node (ref "9VNO2_VOLT_REG") (pin "6") (pinfunction "RT_6") (pintype "input"))
      (node (ref "R13") (pin "2") (pinfunction "2_2") (pintype "passive"))
    )
    (net (code "36") (name "Net-(9VNO2_VOLT_REG-RUN{slash}SS)") (class "Default")
      (node (ref "9VNO2_VOLT_REG") (pin "14") (pinfunction "RUN/SS_14") (pintype "input"))
      (node (ref "C18") (pin "1") (pinfunction "1_1") (pintype "bidirectional"))
      (node (ref "R17") (pin "1") (pinfunction "1_1") (pintype "passive"))
    )
    (net (code "37") (name "Net-(9VNO2_VOLT_REG-SW)") (class "Default")
      (node (ref "9VNO2_VOLT_REG") (pin "12") (pinfunction "SW_12") (pintype "output"))
      (node (ref "9VNO2_VOLT_REG") (pin "9") (pinfunction "DC_9") (pintype "passive"))
      (node (ref "9VNO2_VOLT_REG") (pin "9@2") (pinfunction "DC_9@2") (pintype "passive"))
      (node (ref "C21") (pin "2") (pinfunction "2_2") (pintype "bidirectional"))
      (node (ref "INDUCTOR_6") (pin "1") (pinfunction "1_1") (pintype "passive"))
    )
    (net (code "38") (name "Net-(9VNO2_VOLT_REG-VC)") (class "Default")
      (node (ref "9VNO2_VOLT_REG") (pin "5") (pinfunction "VC_5") (pintype "output"))
      (node (ref "R16") (pin "2") (pinfunction "2_2") (pintype "passive"))
    )
    (net (code "39") (name "Net-(12VNO1_VOLT_REG-BOOST)") (class "Default")
      (node (ref "12VNO1_VOLT_REG") (pin "11") (pinfunction "BOOST_11") (pintype "output"))
      (node (ref "C23") (pin "1") (pinfunction "1_1") (pintype "bidirectional"))
    )
    (net (code "40") (name "Net-(12VNO1_VOLT_REG-FB)") (class "Default")
      (node (ref "12VNO1_VOLT_REG") (pin "3") (pinfunction "FB_3") (pintype "input"))
      (node (ref "R22") (pin "2") (pinfunction "2_2") (pintype "passive"))
      (node (ref "R23") (pin "2") (pinfunction "2_2") (pintype "passive"))
    )
    (net (code "41") (name "Net-(12VNO1_VOLT_REG-RT)") (class "Default")
      (node (ref "12VNO1_VOLT_REG") (pin "6") (pinfunction "RT_6") (pintype "input"))
      (node (ref "R28") (pin "2") (pinfunction "2_2") (pintype "passive"))
    )
    (net (code "42") (name "Net-(12VNO1_VOLT_REG-RUN{slash}SS)") (class "Default")
      (node (ref "12VNO1_VOLT_REG") (pin "14") (pinfunction "RUN/SS_14") (pintype "input"))
      (node (ref "C29") (pin "1") (pinfunction "1_1") (pintype "bidirectional"))
      (node (ref "R30") (pin "1") (pinfunction "1_1") (pintype "passive"))
    )
    (net (code "43") (name "Net-(12VNO1_VOLT_REG-SW)") (class "Default")
      (node (ref "12VNO1_VOLT_REG") (pin "12") (pinfunction "SW_12") (pintype "output"))
      (node (ref "12VNO1_VOLT_REG") (pin "9") (pinfunction "DC_9") (pintype "passive"))
      (node (ref "12VNO1_VOLT_REG") (pin "9@2") (pinfunction "DC_9@2") (pintype "passive"))
      (node (ref "C23") (pin "2") (pinfunction "2_2") (pintype "bidirectional"))
      (node (ref "INDUCTOR_7") (pin "1") (pinfunction "1_1") (pintype "passive"))
    )
    (net (code "44") (name "Net-(12VNO1_VOLT_REG-VC)") (class "Default")
      (node (ref "12VNO1_VOLT_REG") (pin "5") (pinfunction "VC_5") (pintype "output"))
      (node (ref "R29") (pin "2") (pinfunction "2_2") (pintype "passive"))
    )
    (net (code "45") (name "Net-(12VNO2_VOLT_REG-BOOST)") (class "Default")
      (node (ref "12VNO2_VOLT_REG") (pin "11") (pinfunction "BOOST_11") (pintype "output"))
      (node (ref "C25") (pin "1") (pinfunction "1_1") (pintype "bidirectional"))
    )
    (net (code "46") (name "Net-(12VNO2_VOLT_REG-FB)") (class "Default")
      (node (ref "12VNO2_VOLT_REG") (pin "3") (pinfunction "FB_3") (pintype "input"))
      (node (ref "R25") (pin "2") (pinfunction "2_2") (pintype "passive"))
      (node (ref "R26") (pin "2") (pinfunction "2_2") (pintype "passive"))
    )
    (net (code "47") (name "Net-(12VNO2_VOLT_REG-RT)") (class "Default")
      (node (ref "12VNO2_VOLT_REG") (pin "6") (pinfunction "RT_6") (pintype "input"))
      (node (ref "R35") (pin "2") (pinfunction "2_2") (pintype "passive"))
    )
    (net (code "48") (name "Net-(12VNO2_VOLT_REG-RUN{slash}SS)") (class "Default")
      (node (ref "12VNO2_VOLT_REG") (pin "14") (pinfunction "RUN/SS_14") (pintype "input"))
      (node (ref "C36") (pin "1") (pinfunction "1_1") (pintype "bidirectional"))
      (node (ref "R68") (pin "1") (pinfunction "1_1") (pintype "passive"))
    )
    (net (code "49") (name "Net-(12VNO2_VOLT_REG-SW)") (class "Default")
      (node (ref "12VNO2_VOLT_REG") (pin "12") (pinfunction "SW_12") (pintype "output"))
      (node (ref "12VNO2_VOLT_REG") (pin "9") (pinfunction "DC_9") (pintype "passive"))
      (node (ref "12VNO2_VOLT_REG") (pin "9@2") (pinfunction "DC_9@2") (pintype "passive"))
      (node (ref "C25") (pin "2") (pinfunction "2_2") (pintype "bidirectional"))
      (node (ref "INDUCTOR_8") (pin "1") (pinfunction "1_1") (pintype "passive"))
    )
    (net (code "50") (name "Net-(12VNO2_VOLT_REG-VC)") (class "Default")
      (node (ref "12VNO2_VOLT_REG") (pin "5") (pinfunction "VC_5") (pintype "output"))
      (node (ref "R36") (pin "2") (pinfunction "2_2") (pintype "passive"))
    )
    (net (code "51") (name "Net-(C3-Pad1)") (class "Default")
      (node (ref "C3") (pin "1") (pinfunction "1_1") (pintype "bidirectional"))
      (node (ref "R3") (pin "1") (pinfunction "1_1") (pintype "passive"))
    )
    (net (code "52") (name "Net-(C4-Pad1)") (class "Default")
      (node (ref "C4") (pin "1") (pinfunction "1_1") (pintype "bidirectional"))
      (node (ref "R62") (pin "1") (pinfunction "1_1") (pintype "passive"))
    )
    (net (code "53") (name "Net-(C11-Pad1)") (class "Default")
      (node (ref "C11") (pin "1") (pinfunction "1_1") (pintype "bidirectional"))
      (node (ref "R10") (pin "1") (pinfunction "1_1") (pintype "passive"))
    )
    (net (code "54") (name "Net-(C17-Pad1)") (class "Default")
      (node (ref "C17") (pin "1") (pinfunction "1_1") (pintype "bidirectional"))
      (node (ref "R16") (pin "1") (pinfunction "1_1") (pintype "passive"))
    )
    (net (code "55") (name "Net-(C28-Pad1)") (class "Default")
      (node (ref "C28") (pin "1") (pinfunction "1_1") (pintype "bidirectional"))
      (node (ref "R29") (pin "1") (pinfunction "1_1") (pintype "passive"))
    )
    (net (code "56") (name "Net-(C35-Pad1)") (class "Default")
      (node (ref "C35") (pin "1") (pinfunction "1_1") (pintype "bidirectional"))
      (node (ref "R36") (pin "1") (pinfunction "1_1") (pintype "passive"))
    )
    (net (code "57") (name "Net-(J0_VLINE_CONN-Pad2)") (class "Default")
      (node (ref "J0_VLINE_CONN") (pin "2") (pinfunction "2_2") (pintype "bidirectional"))
      (node (ref "R65") (pin "2") (pinfunction "2_2") (pintype "passive"))
    )
    (net (code "58") (name "Net-(J1_5VNO1_CONN-Pad1)") (class "Default")
      (node (ref "J1_5VNO1_CONN") (pin "1") (pinfunction "1_1") (pintype "bidirectional"))
      (node (ref "R14") (pin "1") (pinfunction "1_1") (pintype "passive"))
    )
    (net (code "59") (name "Net-(J2_5VNO2_CONN-Pad1)") (class "Default")
      (node (ref "J2_5VNO2_CONN") (pin "1") (pinfunction "1_1") (pintype "bidirectional"))
      (node (ref "R34") (pin "1") (pinfunction "1_1") (pintype "passive"))
    )
    (net (code "60") (name "Net-(J3_9VNO1_CONN-Pad1)") (class "Default")
      (node (ref "J3_9VNO1_CONN") (pin "1") (pinfunction "1_1") (pintype "bidirectional"))
      (node (ref "R21") (pin "1") (pinfunction "1_1") (pintype "passive"))
    )
    (net (code "61") (name "Net-(J4_9VNO2_CONN-Pad1)") (class "Default")
      (node (ref "J4_9VNO2_CONN") (pin "1") (pinfunction "1_1") (pintype "bidirectional"))
      (node (ref "R64") (pin "1") (pinfunction "1_1") (pintype "passive"))
    )
    (net (code "62") (name "Net-(J5_12VNO1_CONN-Pad2)") (class "Default")
      (node (ref "J5_12VNO1_CONN") (pin "2") (pinfunction "2_2") (pintype "bidirectional"))
      (node (ref "R24") (pin "1") (pinfunction "1_1") (pintype "passive"))
    )
    (net (code "63") (name "Net-(J6_12VNO2_CONN-Pad2)") (class "Default")
      (node (ref "J6_12VNO2_CONN") (pin "2") (pinfunction "2_2") (pintype "bidirectional"))
      (node (ref "R27") (pin "1") (pinfunction "1_1") (pintype "passive"))
    )
    (net (code "64") (name "Net-(Q2-D)") (class "Default")
      (node (ref "Q2") (pin "3") (pinfunction "D_3") (pintype "bidirectional"))
      (node (ref "R65") (pin "1") (pinfunction "1_1") (pintype "passive"))
    )
    (net (code "65") (name "unconnected-(5VNO1_VOLT_REG-PG-Pad1)") (class "Default")
      (node (ref "5VNO1_VOLT_REG") (pin "1") (pinfunction "PG_1") (pintype "open_collector"))
    )
    (net (code "66") (name "unconnected-(5VNO2_VOLT_REG-PG-Pad1)") (class "Default")
      (node (ref "5VNO2_VOLT_REG") (pin "1") (pinfunction "PG_1") (pintype "open_collector"))
    )
    (net (code "67") (name "unconnected-(9VNO1_VOLT_REG-PG-Pad1)") (class "Default")
      (node (ref "9VNO1_VOLT_REG") (pin "1") (pinfunction "PG_1") (pintype "open_collector"))
    )
    (net (code "68") (name "unconnected-(9VNO2_VOLT_REG-PG-Pad1)") (class "Default")
      (node (ref "9VNO2_VOLT_REG") (pin "1") (pinfunction "PG_1") (pintype "open_collector"))
    )
    (net (code "69") (name "unconnected-(12VNO1_VOLT_REG-PG-Pad1)") (class "Default")
      (node (ref "12VNO1_VOLT_REG") (pin "1") (pinfunction "PG_1") (pintype "open_collector"))
    )
    (net (code "70") (name "unconnected-(12VNO2_VOLT_REG-DA-Pad8)") (class "Default")
      (node (ref "12VNO2_VOLT_REG") (pin "8") (pinfunction "DA_8") (pintype "passive"))
    )
    (net (code "71") (name "unconnected-(12VNO2_VOLT_REG-PG-Pad1)") (class "Default")
      (node (ref "12VNO2_VOLT_REG") (pin "1") (pinfunction "PG_1") (pintype "open_collector"))
    )
    (net (code "72") (name "unconnected-(J5_12VNO1_CONN-PadMH1)") (class "Default")
      (node (ref "J5_12VNO1_CONN") (pin "MH1") (pinfunction "MH1_MH1") (pintype "bidirectional"))
    )
    (net (code "73") (name "unconnected-(J5_12VNO1_CONN-PadMH2)") (class "Default")
      (node (ref "J5_12VNO1_CONN") (pin "MH2") (pinfunction "MH2_MH2") (pintype "bidirectional"))
    )
    (net (code "74") (name "unconnected-(J6_12VNO2_CONN-PadMH1)") (class "Default")
      (node (ref "J6_12VNO2_CONN") (pin "MH1") (pinfunction "MH1_MH1") (pintype "bidirectional"))
    )
    (net (code "75") (name "unconnected-(J6_12VNO2_CONN-PadMH2)") (class "Default")
      (node (ref "J6_12VNO2_CONN") (pin "MH2") (pinfunction "MH2_MH2") (pintype "bidirectional"))
    )
  )
)
